# bms_AFE_R00.net
KiCad netlist of a schematic drawn in Altium Designer
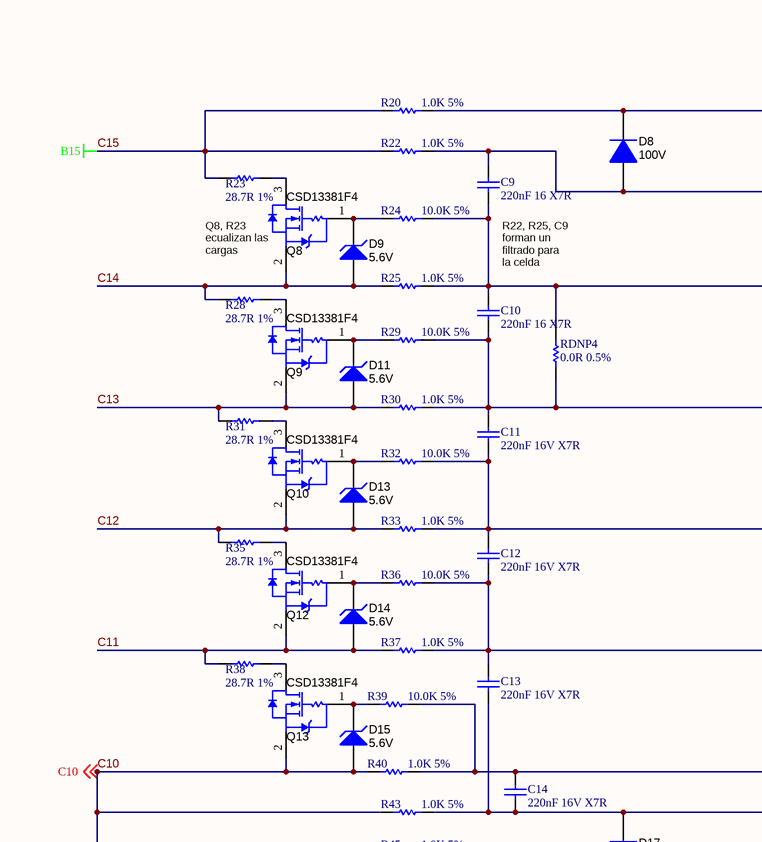
[diagram p0: bms_AFE_R00.SchDoc, top left]
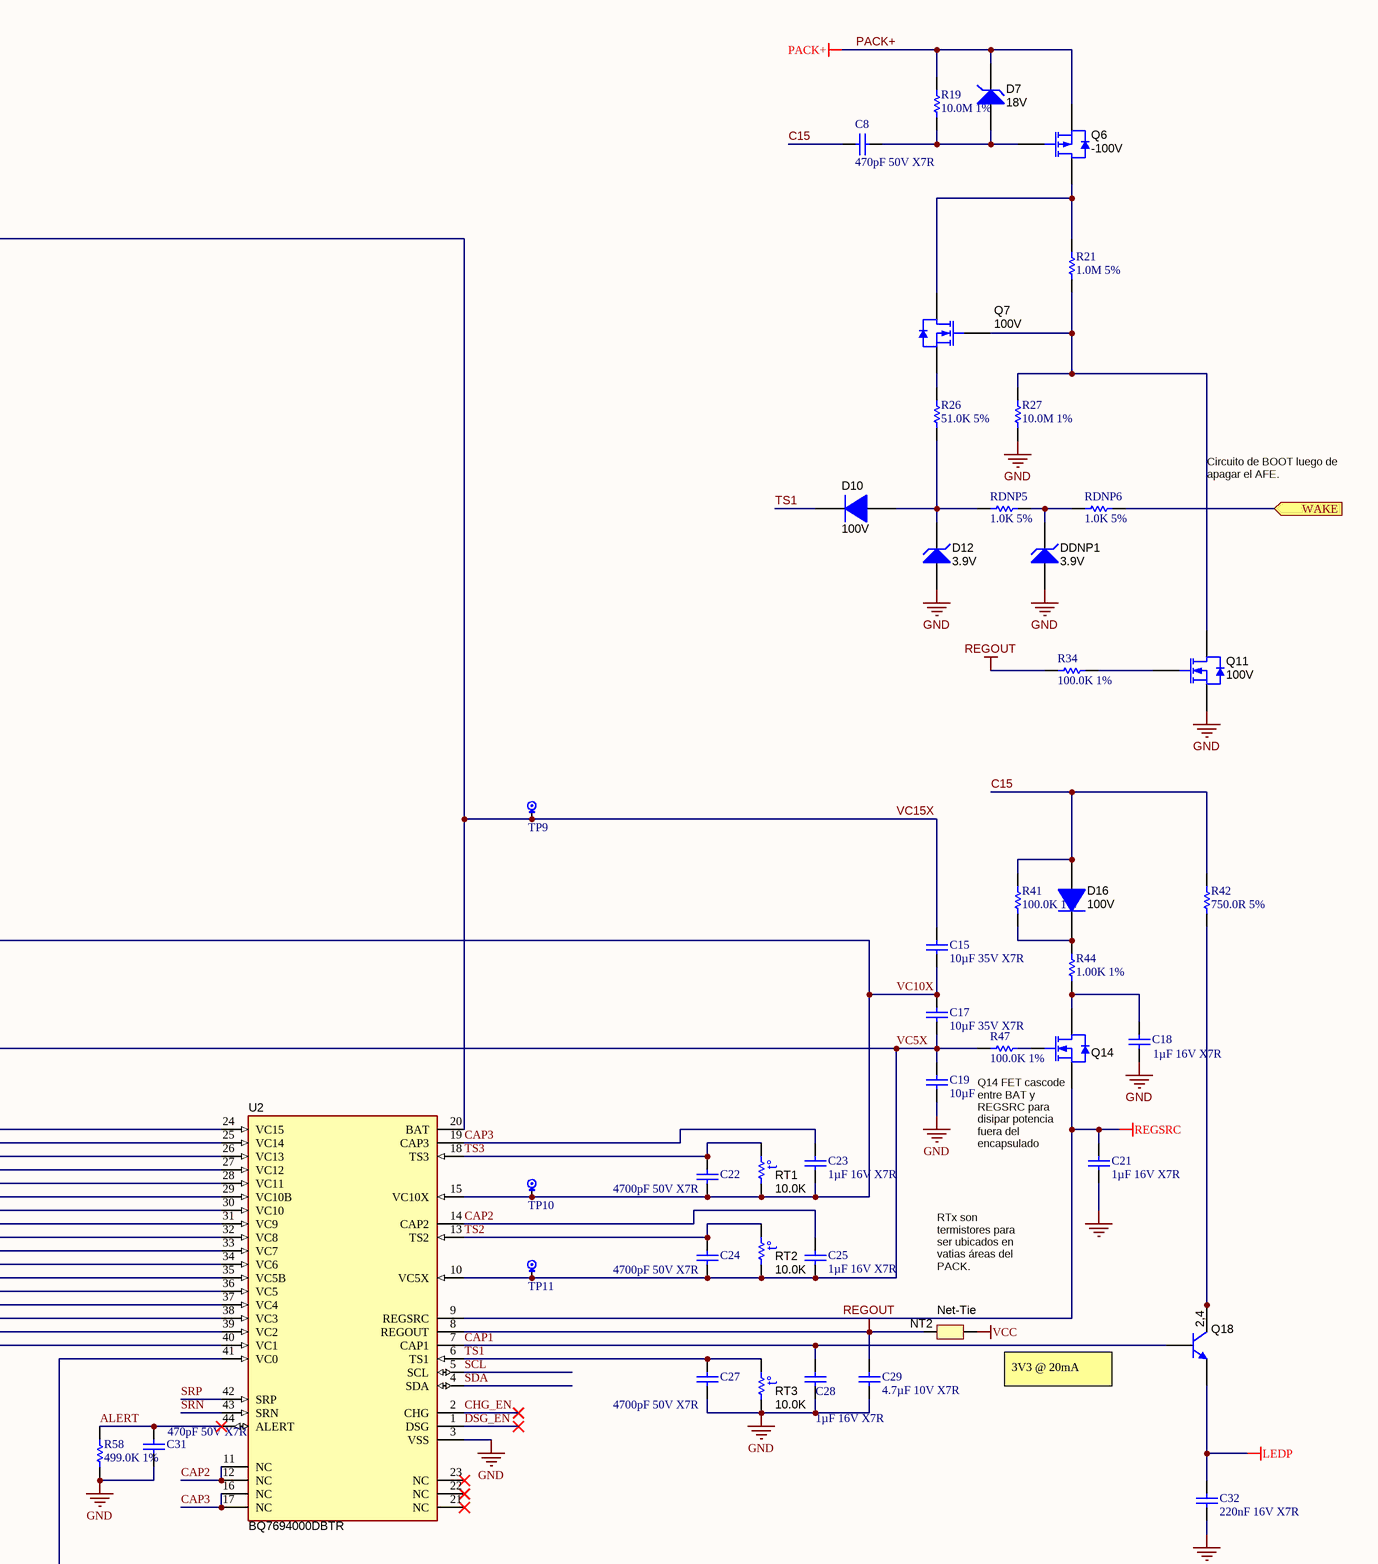
[diagram p1: bms_AFE_R00.SchDoc, top right]
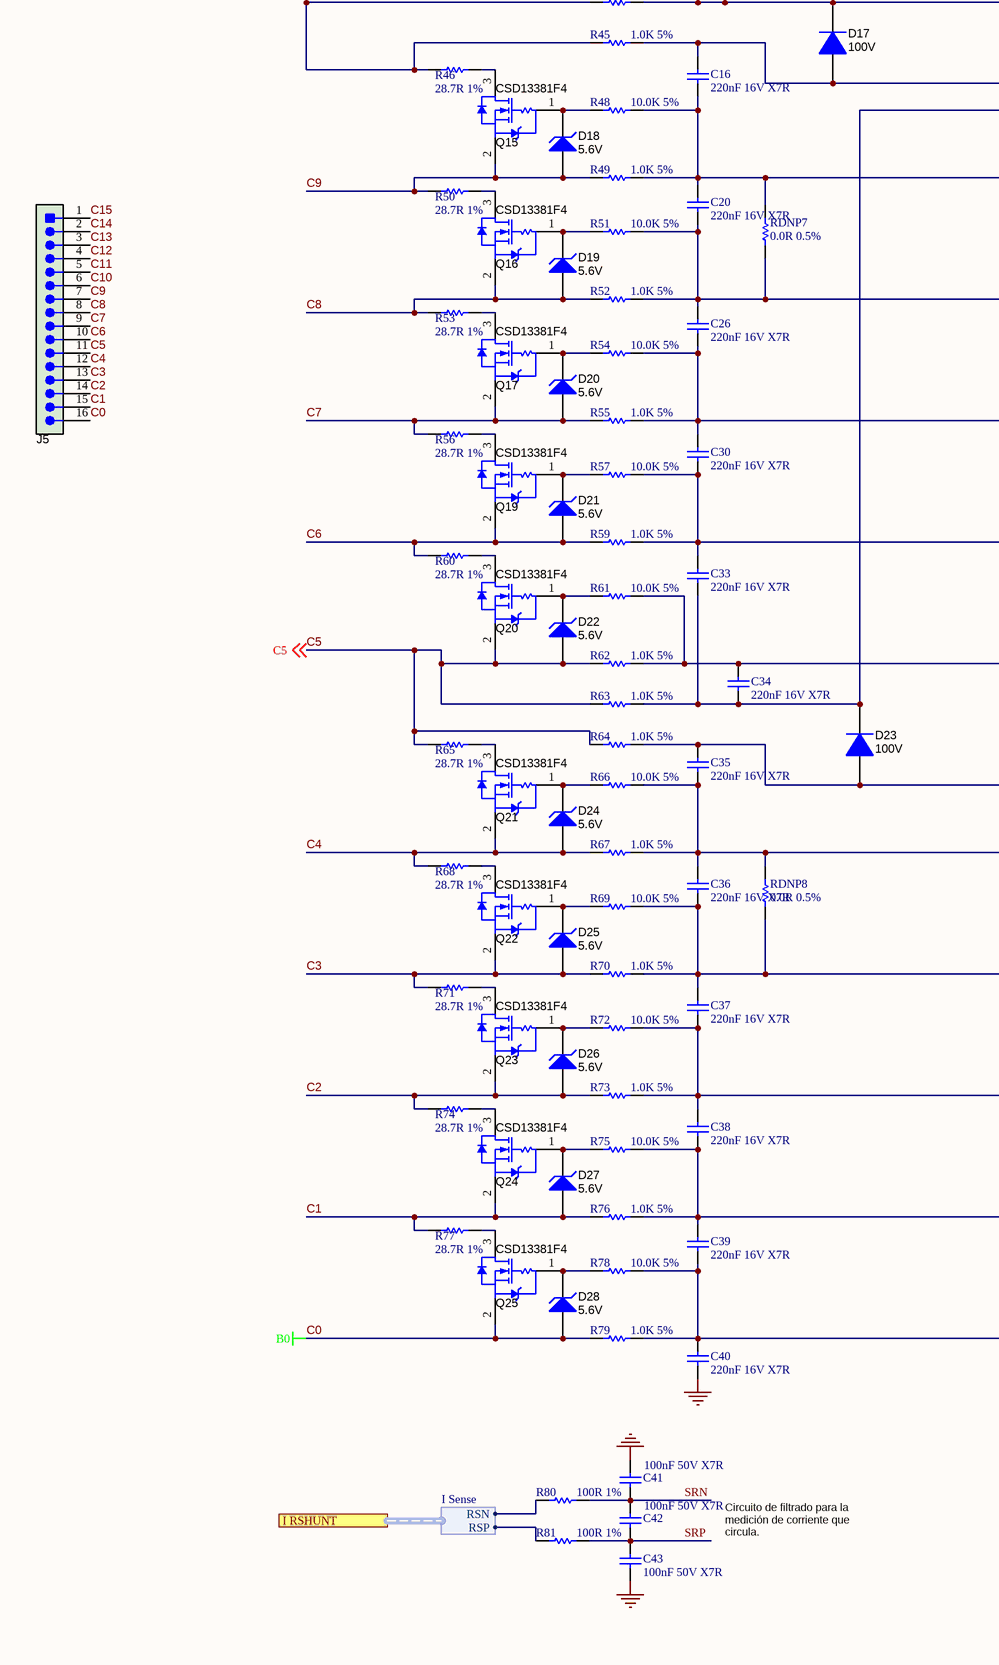
[diagram p2: bms_AFE_R00.SchDoc, bottom left]
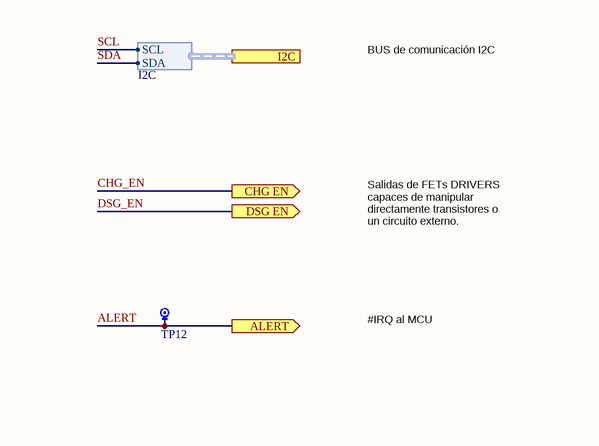
[diagram p3: bms_AFE_R00.SchDoc, bottom right]

(export (version "E")
  (design (tool "Eeschema 10.0.6"))
  (components
    (comp (ref "C8")
      (value "470pF 50V X7R")
      (footprint "C0603")
      (description "Capacitor")
      (libsource (lib "capacitors") (part "Cap 0603"))
    )
    (comp (ref "C9")
      (value "220nF 16 X7R")
      (footprint "C0603")
      (description "Capacitor")
      (libsource (lib "capacitors") (part "Cap 0603"))
    )
    (comp (ref "C10")
      (value "220nF 16 X7R")
      (footprint "C0603")
      (description "Capacitor")
      (libsource (lib "capacitors") (part "Cap 0603"))
    )
    (comp (ref "C11")
      (value "220nF 16V X7R")
      (footprint "C0603")
      (description "Capacitor")
      (libsource (lib "capacitors") (part "Cap 0603"))
    )
    (comp (ref "C12")
      (value "220nF 16V X7R")
      (footprint "C0603")
      (description "Capacitor")
      (libsource (lib "capacitors") (part "Cap 0603"))
    )
    (comp (ref "C13")
      (value "220nF 16V X7R")
      (footprint "C0603")
      (description "Capacitor")
      (libsource (lib "capacitors") (part "Cap 0603"))
    )
    (comp (ref "C14")
      (value "220nF 16V X7R")
      (footprint "C0603")
      (description "Capacitor")
      (libsource (lib "capacitors") (part "Cap 0603"))
    )
    (comp (ref "C15")
      (value "10µF 35V X7R")
      (footprint "1210_270")
      (description "Capacitor")
      (libsource (lib "capacitors") (part "Cap 1210"))
    )
    (comp (ref "C16")
      (value "220nF 16V X7R")
      (footprint "C0603")
      (description "Capacitor")
      (libsource (lib "capacitors") (part "Cap 0603"))
    )
    (comp (ref "C17")
      (value "10µF 35V X7R")
      (footprint "1210_270")
      (description "Capacitor")
      (libsource (lib "capacitors") (part "Cap 1210"))
    )
    (comp (ref "C18")
      (value "1µF 16V X7R")
      (footprint "0805_HV_2")
      (description "Capacitor")
      (libsource (lib "capacitors") (part "Cap 0805_HV"))
    )
    (comp (ref "C19")
      (value "10µF")
      (footprint "1210_270")
      (description "Capacitor")
      (libsource (lib "capacitors") (part "Cap 1210"))
    )
    (comp (ref "C20")
      (value "220nF 16V X7R")
      (footprint "C0603")
      (description "Capacitor")
      (libsource (lib "capacitors") (part "Cap 0603"))
    )
    (comp (ref "C21")
      (value "1µF 16V X7R")
      (footprint "0805")
      (description "Capacitor")
      (libsource (lib "capacitors") (part "Cap 0805"))
    )
    (comp (ref "C22")
      (value "4700pF 50V X7R")
      (footprint "C0603")
      (description "Capacitor")
      (libsource (lib "capacitors") (part "Cap 0603"))
    )
    (comp (ref "C23")
      (value "1µF 16V X7R")
      (footprint "C0603")
      (description "Capacitor")
      (libsource (lib "capacitors") (part "Cap 0603"))
    )
    (comp (ref "C24")
      (value "4700pF 50V X7R")
      (footprint "C0603")
      (description "Capacitor")
      (libsource (lib "capacitors") (part "Cap 0603"))
    )
    (comp (ref "C25")
      (value "1µF 16V X7R")
      (footprint "C0603")
      (description "Capacitor")
      (libsource (lib "capacitors") (part "Cap 0603"))
    )
    (comp (ref "C26")
      (value "220nF 16V X7R")
      (footprint "C0603")
      (description "Capacitor")
      (libsource (lib "capacitors") (part "Cap 0603"))
    )
    (comp (ref "C27")
      (value "4700pF 50V X7R")
      (footprint "C0603")
      (description "Capacitor")
      (libsource (lib "capacitors") (part "Cap 0603"))
    )
    (comp (ref "C28")
      (value "1µF 16V X7R")
      (footprint "C0603")
      (description "Capacitor")
      (libsource (lib "capacitors") (part "Cap 0603"))
    )
    (comp (ref "C29")
      (value "4.7µF 10V X7R")
      (footprint "0805_HV_2")
      (description "Capacitor")
      (libsource (lib "capacitors") (part "Cap 0805_HV"))
    )
    (comp (ref "C30")
      (value "220nF 16V X7R")
      (footprint "C0603")
      (description "Capacitor")
      (libsource (lib "capacitors") (part "Cap 0603"))
    )
    (comp (ref "C31")
      (value "470pF 50V X7R")
      (footprint "C0603")
      (description "Capacitor")
      (libsource (lib "capacitors") (part "Cap 0603"))
    )
    (comp (ref "C32")
      (value "220nF 16V X7R")
      (footprint "C0603")
      (description "Capacitor")
      (libsource (lib "capacitors") (part "Cap 0603"))
    )
    (comp (ref "C33")
      (value "220nF 16V X7R")
      (footprint "C0603")
      (description "Capacitor")
      (libsource (lib "capacitors") (part "Cap 0603"))
    )
    (comp (ref "C34")
      (value "220nF 16V X7R")
      (footprint "C0603")
      (description "Capacitor")
      (libsource (lib "capacitors") (part "Cap 0603"))
    )
    (comp (ref "C35")
      (value "220nF 16V X7R")
      (footprint "C0603")
      (description "Capacitor")
      (libsource (lib "capacitors") (part "Cap 0603"))
    )
    (comp (ref "C36")
      (value "220nF 16V X7R")
      (footprint "C0603")
      (description "Capacitor")
      (libsource (lib "capacitors") (part "Cap 0603"))
    )
    (comp (ref "C37")
      (value "220nF 16V X7R")
      (footprint "C0603")
      (description "Capacitor")
      (libsource (lib "capacitors") (part "Cap 0603"))
    )
    (comp (ref "C38")
      (value "220nF 16V X7R")
      (footprint "C0603")
      (description "Capacitor")
      (libsource (lib "capacitors") (part "Cap 0603"))
    )
    (comp (ref "C39")
      (value "220nF 16V X7R")
      (footprint "C0603")
      (description "Capacitor")
      (libsource (lib "capacitors") (part "Cap 0603"))
    )
    (comp (ref "C40")
      (value "220nF 16V X7R")
      (footprint "C0603")
      (description "Capacitor")
      (libsource (lib "capacitors") (part "Cap 0603"))
    )
    (comp (ref "C41")
      (value "100nF 50V X7R")
      (footprint "C0603")
      (description "Capacitor")
      (libsource (lib "capacitors") (part "Cap 0603"))
    )
    (comp (ref "C42")
      (value "100nF 50V X7R")
      (footprint "C0603")
      (description "Capacitor")
      (libsource (lib "capacitors") (part "Cap 0603"))
    )
    (comp (ref "C43")
      (value "100nF 50V X7R")
      (footprint "C0603")
      (description "Capacitor")
      (libsource (lib "capacitors") (part "Cap 0603"))
    )
    (comp (ref "D7")
      (value "18V")
      (footprint "sod-323")
      (description "Diode, Zener, 18 V, 200 mW, SOD-323")
      (fields
        (field (name "PARTNUMBER") "MMSZ5248BS-7-F")
        (field (name "MANUFACTURER") "Diodes Inc.")
        (field (name "SYMBOLCREATOR") "a0412235")
        (field (name "PUBLISHER") "Texas Instruments")
      )
      (libsource (lib "diodes") (part "MMSZ5248BS-7-F"))
    )
    (comp (ref "D8")
      (value "100V")
      (footprint "SOD-123")
      (description "Diode, Ultrafast, 100V, 0.15A, SOD-123")
      (fields
        (field (name "PARTNUMBER") "1N4148W-7-F")
        (field (name "MANUFACTURER") "Diodes Inc.")
        (field (name "PUBLISHER") "Texas Instruments")
      )
      (libsource (lib "diodes") (part "1N4148W-7-F"))
    )
    (comp (ref "D9")
      (value "5.6V")
      (footprint "sod-323")
      (description "Diode, Zener, 5.6V, 200mW, SOD-323")
      (fields
        (field (name "PARTNUMBER") "MMSZ5232BS-7-F")
        (field (name "MANUFACTURER") "Diodes Inc.")
        (field (name "PUBLISHER") "Texas Instruments")
      )
      (libsource (lib "diodes") (part "MMSZ5232BS-7-F"))
    )
    (comp (ref "D10")
      (value "100V")
      (footprint "SOD-123")
      (description "Diode, Ultrafast, 100V, 0.15A, SOD-123")
      (fields
        (field (name "PARTNUMBER") "1N4148W-7-F")
        (field (name "MANUFACTURER") "Diodes Inc.")
        (field (name "PUBLISHER") "Texas Instruments")
      )
      (libsource (lib "diodes") (part "1N4148W-7-F"))
    )
    (comp (ref "D11")
      (value "5.6V")
      (footprint "sod-323")
      (description "Diode, Zener, 5.6V, 200mW, SOD-323")
      (fields
        (field (name "PARTNUMBER") "MMSZ5232BS-7-F")
        (field (name "MANUFACTURER") "Diodes Inc.")
        (field (name "PUBLISHER") "Texas Instruments")
      )
      (libsource (lib "diodes") (part "MMSZ5232BS-7-F"))
    )
    (comp (ref "D12")
      (value "3.9V")
      (footprint "sod-323")
      (description "Diode, Zener, 3.9 V, 200 mW, SOD-323")
      (fields
        (field (name "PARTNUMBER") "MMSZ5228BS-7-F")
        (field (name "MANUFACTURER") "Diodes Inc.")
        (field (name "SYMBOLCREATOR") "a0412235")
        (field (name "PUBLISHER") "Texas Instruments")
      )
      (libsource (lib "diodes") (part "MMSZ5228BS-7-F"))
    )
    (comp (ref "D13")
      (value "5.6V")
      (footprint "sod-323")
      (description "Diode, Zener, 5.6V, 200mW, SOD-323")
      (fields
        (field (name "PARTNUMBER") "MMSZ5232BS-7-F")
        (field (name "MANUFACTURER") "Diodes Inc.")
        (field (name "PUBLISHER") "Texas Instruments")
      )
      (libsource (lib "diodes") (part "MMSZ5232BS-7-F"))
    )
    (comp (ref "D14")
      (value "5.6V")
      (footprint "sod-323")
      (description "Diode, Zener, 5.6V, 200mW, SOD-323")
      (fields
        (field (name "PARTNUMBER") "MMSZ5232BS-7-F")
        (field (name "MANUFACTURER") "Diodes Inc.")
        (field (name "PUBLISHER") "Texas Instruments")
      )
      (libsource (lib "diodes") (part "MMSZ5232BS-7-F"))
    )
    (comp (ref "D15")
      (value "5.6V")
      (footprint "sod-323")
      (description "Diode, Zener, 5.6V, 200mW, SOD-323")
      (fields
        (field (name "PARTNUMBER") "MMSZ5232BS-7-F")
        (field (name "MANUFACTURER") "Diodes Inc.")
        (field (name "PUBLISHER") "Texas Instruments")
      )
      (libsource (lib "diodes") (part "MMSZ5232BS-7-F"))
    )
    (comp (ref "D16")
      (value "100V")
      (footprint "SOD-123")
      (description "Diode, Ultrafast, 100V, 0.15A, SOD-123")
      (fields
        (field (name "PARTNUMBER") "1N4148W-7-F")
        (field (name "MANUFACTURER") "Diodes Inc.")
        (field (name "PUBLISHER") "Texas Instruments")
      )
      (libsource (lib "diodes") (part "1N4148W-7-F"))
    )
    (comp (ref "D17")
      (value "100V")
      (footprint "SOD-123")
      (description "Diode, Ultrafast, 100V, 0.15A, SOD-123")
      (fields
        (field (name "PARTNUMBER") "1N4148W-7-F")
        (field (name "MANUFACTURER") "Diodes Inc.")
        (field (name "PUBLISHER") "Texas Instruments")
      )
      (libsource (lib "diodes") (part "1N4148W-7-F"))
    )
    (comp (ref "D18")
      (value "5.6V")
      (footprint "sod-323")
      (description "Diode, Zener, 5.6V, 200mW, SOD-323")
      (fields
        (field (name "PARTNUMBER") "MMSZ5232BS-7-F")
        (field (name "MANUFACTURER") "Diodes Inc.")
        (field (name "PUBLISHER") "Texas Instruments")
      )
      (libsource (lib "diodes") (part "MMSZ5232BS-7-F"))
    )
    (comp (ref "D19")
      (value "5.6V")
      (footprint "sod-323")
      (description "Diode, Zener, 5.6V, 200mW, SOD-323")
      (fields
        (field (name "PARTNUMBER") "MMSZ5232BS-7-F")
        (field (name "MANUFACTURER") "Diodes Inc.")
        (field (name "PUBLISHER") "Texas Instruments")
      )
      (libsource (lib "diodes") (part "MMSZ5232BS-7-F"))
    )
    (comp (ref "D20")
      (value "5.6V")
      (footprint "sod-323")
      (description "Diode, Zener, 5.6V, 200mW, SOD-323")
      (fields
        (field (name "PARTNUMBER") "MMSZ5232BS-7-F")
        (field (name "MANUFACTURER") "Diodes Inc.")
        (field (name "PUBLISHER") "Texas Instruments")
      )
      (libsource (lib "diodes") (part "MMSZ5232BS-7-F"))
    )
    (comp (ref "D21")
      (value "5.6V")
      (footprint "sod-323")
      (description "Diode, Zener, 5.6V, 200mW, SOD-323")
      (fields
        (field (name "PARTNUMBER") "MMSZ5232BS-7-F")
        (field (name "MANUFACTURER") "Diodes Inc.")
        (field (name "PUBLISHER") "Texas Instruments")
      )
      (libsource (lib "diodes") (part "MMSZ5232BS-7-F"))
    )
    (comp (ref "D22")
      (value "5.6V")
      (footprint "sod-323")
      (description "Diode, Zener, 5.6V, 200mW, SOD-323")
      (fields
        (field (name "PARTNUMBER") "MMSZ5232BS-7-F")
        (field (name "MANUFACTURER") "Diodes Inc.")
        (field (name "PUBLISHER") "Texas Instruments")
      )
      (libsource (lib "diodes") (part "MMSZ5232BS-7-F"))
    )
    (comp (ref "D23")
      (value "100V")
      (footprint "SOD-123")
      (description "Diode, Ultrafast, 100V, 0.15A, SOD-123")
      (fields
        (field (name "PARTNUMBER") "1N4148W-7-F")
        (field (name "MANUFACTURER") "Diodes Inc.")
        (field (name "PUBLISHER") "Texas Instruments")
      )
      (libsource (lib "diodes") (part "1N4148W-7-F"))
    )
    (comp (ref "D24")
      (value "5.6V")
      (footprint "sod-323")
      (description "Diode, Zener, 5.6V, 200mW, SOD-323")
      (fields
        (field (name "PARTNUMBER") "MMSZ5232BS-7-F")
        (field (name "MANUFACTURER") "Diodes Inc.")
        (field (name "PUBLISHER") "Texas Instruments")
      )
      (libsource (lib "diodes") (part "MMSZ5232BS-7-F"))
    )
    (comp (ref "D25")
      (value "5.6V")
      (footprint "sod-323")
      (description "Diode, Zener, 5.6V, 200mW, SOD-323")
      (fields
        (field (name "PARTNUMBER") "MMSZ5232BS-7-F")
        (field (name "MANUFACTURER") "Diodes Inc.")
        (field (name "PUBLISHER") "Texas Instruments")
      )
      (libsource (lib "diodes") (part "MMSZ5232BS-7-F"))
    )
    (comp (ref "D26")
      (value "5.6V")
      (footprint "sod-323")
      (description "Diode, Zener, 5.6V, 200mW, SOD-323")
      (fields
        (field (name "PARTNUMBER") "MMSZ5232BS-7-F")
        (field (name "MANUFACTURER") "Diodes Inc.")
        (field (name "PUBLISHER") "Texas Instruments")
      )
      (libsource (lib "diodes") (part "MMSZ5232BS-7-F"))
    )
    (comp (ref "D27")
      (value "5.6V")
      (footprint "sod-323")
      (description "Diode, Zener, 5.6V, 200mW, SOD-323")
      (fields
        (field (name "PARTNUMBER") "MMSZ5232BS-7-F")
        (field (name "MANUFACTURER") "Diodes Inc.")
        (field (name "PUBLISHER") "Texas Instruments")
      )
      (libsource (lib "diodes") (part "MMSZ5232BS-7-F"))
    )
    (comp (ref "D28")
      (value "5.6V")
      (footprint "sod-323")
      (description "Diode, Zener, 5.6V, 200mW, SOD-323")
      (fields
        (field (name "PARTNUMBER") "MMSZ5232BS-7-F")
        (field (name "MANUFACTURER") "Diodes Inc.")
        (field (name "PUBLISHER") "Texas Instruments")
      )
      (libsource (lib "diodes") (part "MMSZ5232BS-7-F"))
    )
    (comp (ref "DDNP1")
      (value "3.9V")
      (footprint "sod-323")
      (description "Diode, Zener, 3.9 V, 200 mW, SOD-323")
      (fields
        (field (name "PARTNUMBER") "MMSZ5228BS-7-F")
        (field (name "MANUFACTURER") "Diodes Inc.")
        (field (name "SYMBOLCREATOR") "a0412235")
        (field (name "PUBLISHER") "Texas Instruments")
      )
      (libsource (lib "diodes") (part "MMSZ5228BS-7-F"))
    )
    (comp (ref "J5")
      (value "395021011")
      (footprint "HEADER_395021016")
      (description "Terminal block, 3.5mm, 16x1, R/A, TH")
      (fields
        (field (name "MANUFACTURER") "Molex")
        (field (name "SYMBOLCREATOR") "a0799628")
        (field (name "PUBLISHER") "Texas Instruments")
      )
      (libsource (lib "connectors") (part "395021016"))
    )
    (comp (ref "NT2")
      (value "Net-Tie")
      (footprint "Net-Tie_50milWide_30milLong")
      (description "Single point connection between nets.")
      (fields (field (name "SYMBOLCREATOR") "codlsc") (field (name "PUBLISHER") "Texas Instruments"))
      (libsource (lib "connectors") (part "Net-Tie"))
    )
    (comp (ref "Q6")
      (value "-100V")
      (footprint "SOT-23")
      (description "MOSFET, P-CH, -100V, -0.6A, SOT-23")
      (fields
        (field (name "PARTNUMBER") "ZXMP10A13FTA")
        (field (name "MANUFACTURER") "Diodes Inc.")
        (field (name "PUBLISHER") "Texas Instruments")
      )
      (libsource (lib "pmos") (part "ZXMP10A13FTA"))
    )
    (comp (ref "Q7")
      (value "100V")
      (footprint "SOT-23")
      (description "MOSFET, N-CH, 100V, 0.17A, SOT-23")
      (fields
        (field (name "PARTNUMBER") "BSS123")
        (field (name "MANUFACTURER") "Fairchild Semiconductor")
        (field (name "PUBLISHER") "Texas Instruments")
      )
      (libsource (lib "nmos") (part "BSS123"))
    )
    (comp (ref "Q8")
      (value "CSD13381F4")
      (footprint "YJC0003A")
      (description "MOSFET, N/P-CH, 12 V, 2.1 A, 1.0x0.35x0.6mm")
      (fields
        (field (name "MANUFACTURER") "Texas Instruments")
        (field (name "SYMBOLCREATOR") "a0411947")
        (field (name "PUBLISHER") "Texas Instruments")
      )
      (libsource (lib "nmos") (part "CSD13381F4"))
    )
    (comp (ref "Q9")
      (value "CSD13381F4")
      (footprint "YJC0003A")
      (description "MOSFET, N/P-CH, 12 V, 2.1 A, 1.0x0.35x0.6mm")
      (fields
        (field (name "MANUFACTURER") "Texas Instruments")
        (field (name "SYMBOLCREATOR") "a0411947")
        (field (name "PUBLISHER") "Texas Instruments")
      )
      (libsource (lib "nmos") (part "CSD13381F4"))
    )
    (comp (ref "Q10")
      (value "CSD13381F4")
      (footprint "YJC0003A")
      (description "MOSFET, N/P-CH, 12 V, 2.1 A, 1.0x0.35x0.6mm")
      (fields
        (field (name "MANUFACTURER") "Texas Instruments")
        (field (name "SYMBOLCREATOR") "a0411947")
        (field (name "PUBLISHER") "Texas Instruments")
      )
      (libsource (lib "nmos") (part "CSD13381F4"))
    )
    (comp (ref "Q11")
      (value "100V")
      (footprint "SOT-23")
      (description "MOSFET, N-CH, 100V, 0.17A, SOT-23")
      (fields
        (field (name "PARTNUMBER") "BSS123")
        (field (name "MANUFACTURER") "Fairchild Semiconductor")
        (field (name "PUBLISHER") "Texas Instruments")
      )
      (libsource (lib "nmos") (part "BSS123"))
    )
    (comp (ref "Q12")
      (value "CSD13381F4")
      (footprint "YJC0003A")
      (description "MOSFET, N/P-CH, 12 V, 2.1 A, 1.0x0.35x0.6mm")
      (fields
        (field (name "MANUFACTURER") "Texas Instruments")
        (field (name "SYMBOLCREATOR") "a0411947")
        (field (name "PUBLISHER") "Texas Instruments")
      )
      (libsource (lib "nmos") (part "CSD13381F4"))
    )
    (comp (ref "Q13")
      (value "CSD13381F4")
      (footprint "YJC0003A")
      (description "MOSFET, N/P-CH, 12 V, 2.1 A, 1.0x0.35x0.6mm")
      (fields
        (field (name "MANUFACTURER") "Texas Instruments")
        (field (name "SYMBOLCREATOR") "a0411947")
        (field (name "PUBLISHER") "Texas Instruments")
      )
      (libsource (lib "nmos") (part "CSD13381F4"))
    )
    (comp (ref "Q14")
      (value "BST82,215")
      (footprint "SOT-23")
      (description "MOSFET, N-CH, 100 V, 0.19 A, SOT-23")
      (fields
        (field (name "MANUFACTURER") "NXP Semiconductor")
        (field (name "PUBLISHER") "Texas Instruments")
      )
      (libsource (lib "nmos") (part "BST82,215"))
    )
    (comp (ref "Q15")
      (value "CSD13381F4")
      (footprint "YJC0003A")
      (description "MOSFET, N/P-CH, 12 V, 2.1 A, 1.0x0.35x0.6mm")
      (fields
        (field (name "MANUFACTURER") "Texas Instruments")
        (field (name "SYMBOLCREATOR") "a0411947")
        (field (name "PUBLISHER") "Texas Instruments")
      )
      (libsource (lib "nmos") (part "CSD13381F4"))
    )
    (comp (ref "Q16")
      (value "CSD13381F4")
      (footprint "YJC0003A")
      (description "MOSFET, N/P-CH, 12 V, 2.1 A, 1.0x0.35x0.6mm")
      (fields
        (field (name "MANUFACTURER") "Texas Instruments")
        (field (name "SYMBOLCREATOR") "a0411947")
        (field (name "PUBLISHER") "Texas Instruments")
      )
      (libsource (lib "nmos") (part "CSD13381F4"))
    )
    (comp (ref "Q17")
      (value "CSD13381F4")
      (footprint "YJC0003A")
      (description "MOSFET, N/P-CH, 12 V, 2.1 A, 1.0x0.35x0.6mm")
      (fields
        (field (name "MANUFACTURER") "Texas Instruments")
        (field (name "SYMBOLCREATOR") "a0411947")
        (field (name "PUBLISHER") "Texas Instruments")
      )
      (libsource (lib "nmos") (part "CSD13381F4"))
    )
    (comp (ref "Q18")
      (value "ZXTN19100CZTA")
      (footprint "SOT-89-3")
      (description "Transistor, NPN, 100 V, 5.25 A, SOT-89")
      (fields
        (field (name "MANUFACTURER") "Diodes Inc.")
        (field (name "SYMBOLCREATOR") "a0412235")
        (field (name "PUBLISHER") "Texas Instruments")
      )
      (libsource (lib "npn") (part "ZXTN19100CZTA, Diodes Inc."))
    )
    (comp (ref "Q19")
      (value "CSD13381F4")
      (footprint "YJC0003A")
      (description "MOSFET, N/P-CH, 12 V, 2.1 A, 1.0x0.35x0.6mm")
      (fields
        (field (name "MANUFACTURER") "Texas Instruments")
        (field (name "SYMBOLCREATOR") "a0411947")
        (field (name "PUBLISHER") "Texas Instruments")
      )
      (libsource (lib "nmos") (part "CSD13381F4"))
    )
    (comp (ref "Q20")
      (value "CSD13381F4")
      (footprint "YJC0003A")
      (description "MOSFET, N/P-CH, 12 V, 2.1 A, 1.0x0.35x0.6mm")
      (fields
        (field (name "MANUFACTURER") "Texas Instruments")
        (field (name "SYMBOLCREATOR") "a0411947")
        (field (name "PUBLISHER") "Texas Instruments")
      )
      (libsource (lib "nmos") (part "CSD13381F4"))
    )
    (comp (ref "Q21")
      (value "CSD13381F4")
      (footprint "YJC0003A")
      (description "MOSFET, N/P-CH, 12 V, 2.1 A, 1.0x0.35x0.6mm")
      (fields
        (field (name "MANUFACTURER") "Texas Instruments")
        (field (name "SYMBOLCREATOR") "a0411947")
        (field (name "PUBLISHER") "Texas Instruments")
      )
      (libsource (lib "nmos") (part "CSD13381F4"))
    )
    (comp (ref "Q22")
      (value "CSD13381F4")
      (footprint "YJC0003A")
      (description "MOSFET, N/P-CH, 12 V, 2.1 A, 1.0x0.35x0.6mm")
      (fields
        (field (name "MANUFACTURER") "Texas Instruments")
        (field (name "SYMBOLCREATOR") "a0411947")
        (field (name "PUBLISHER") "Texas Instruments")
      )
      (libsource (lib "nmos") (part "CSD13381F4"))
    )
    (comp (ref "Q23")
      (value "CSD13381F4")
      (footprint "YJC0003A")
      (description "MOSFET, N/P-CH, 12 V, 2.1 A, 1.0x0.35x0.6mm")
      (fields
        (field (name "MANUFACTURER") "Texas Instruments")
        (field (name "SYMBOLCREATOR") "a0411947")
        (field (name "PUBLISHER") "Texas Instruments")
      )
      (libsource (lib "nmos") (part "CSD13381F4"))
    )
    (comp (ref "Q24")
      (value "CSD13381F4")
      (footprint "YJC0003A")
      (description "MOSFET, N/P-CH, 12 V, 2.1 A, 1.0x0.35x0.6mm")
      (fields
        (field (name "MANUFACTURER") "Texas Instruments")
        (field (name "SYMBOLCREATOR") "a0411947")
        (field (name "PUBLISHER") "Texas Instruments")
      )
      (libsource (lib "nmos") (part "CSD13381F4"))
    )
    (comp (ref "Q25")
      (value "CSD13381F4")
      (footprint "YJC0003A")
      (description "MOSFET, N/P-CH, 12 V, 2.1 A, 1.0x0.35x0.6mm")
      (fields
        (field (name "MANUFACTURER") "Texas Instruments")
        (field (name "SYMBOLCREATOR") "a0411947")
        (field (name "PUBLISHER") "Texas Instruments")
      )
      (libsource (lib "nmos") (part "CSD13381F4"))
    )
    (comp (ref "R19")
      (value "10.0M 1%")
      (footprint "R0603")
      (description "Resistor")
      (libsource (lib "resistors") (part "Res"))
    )
    (comp (ref "R20")
      (value "1.0K 5%")
      (footprint "R0603")
      (description "Resistor")
      (libsource (lib "resistors") (part "Res"))
    )
    (comp (ref "R21")
      (value "1.0M 5%")
      (footprint "R0603")
      (description "Resistor")
      (libsource (lib "resistors") (part "Res"))
    )
    (comp (ref "R22")
      (value "1.0K 5%")
      (footprint "R0603")
      (description "Resistor")
      (libsource (lib "resistors") (part "Res"))
    )
    (comp (ref "R23")
      (value "28.7R 1%")
      (footprint "2512")
      (description "Resistor")
      (libsource (lib "resistors") (part "Res"))
    )
    (comp (ref "R24")
      (value "10.0K 5%")
      (footprint "R0603")
      (description "Resistor")
      (libsource (lib "resistors") (part "Res"))
    )
    (comp (ref "R25")
      (value "1.0K 5%")
      (footprint "R0603")
      (description "Resistor")
      (libsource (lib "resistors") (part "Res"))
    )
    (comp (ref "R26")
      (value "51.0K 5%")
      (footprint "R0603")
      (description "Resistor")
      (libsource (lib "resistors") (part "Res"))
    )
    (comp (ref "R27")
      (value "10.0M 1%")
      (footprint "R0603")
      (description "Resistor")
      (libsource (lib "resistors") (part "Res"))
    )
    (comp (ref "R28")
      (value "28.7R 1%")
      (footprint "2512")
      (description "Resistor")
      (libsource (lib "resistors") (part "Res"))
    )
    (comp (ref "R29")
      (value "10.0K 5%")
      (footprint "R0603")
      (description "Resistor")
      (libsource (lib "resistors") (part "Res"))
    )
    (comp (ref "R30")
      (value "1.0K 5%")
      (footprint "R0603")
      (description "Resistor")
      (libsource (lib "resistors") (part "Res"))
    )
    (comp (ref "R31")
      (value "28.7R 1%")
      (footprint "2512")
      (description "Resistor")
      (libsource (lib "resistors") (part "Res"))
    )
    (comp (ref "R32")
      (value "10.0K 5%")
      (footprint "R0603")
      (description "Resistor")
      (libsource (lib "resistors") (part "Res"))
    )
    (comp (ref "R33")
      (value "1.0K 5%")
      (footprint "R0603")
      (description "Resistor")
      (libsource (lib "resistors") (part "Res"))
    )
    (comp (ref "R34")
      (value "100.0K 1%")
      (footprint "0805_HV_2")
      (description "Resistor")
      (libsource (lib "resistors") (part "Res"))
    )
    (comp (ref "R35")
      (value "28.7R 1%")
      (footprint "2512")
      (description "Resistor")
      (libsource (lib "resistors") (part "Res"))
    )
    (comp (ref "R36")
      (value "10.0K 5%")
      (footprint "R0603")
      (description "Resistor")
      (libsource (lib "resistors") (part "Res"))
    )
    (comp (ref "R37")
      (value "1.0K 5%")
      (footprint "R0603")
      (description "Resistor")
      (libsource (lib "resistors") (part "Res"))
    )
    (comp (ref "R38")
      (value "28.7R 1%")
      (footprint "2512")
      (description "Resistor")
      (libsource (lib "resistors") (part "Res"))
    )
    (comp (ref "R39")
      (value "10.0K 5%")
      (footprint "R0603")
      (description "Resistor")
      (libsource (lib "resistors") (part "Res"))
    )
    (comp (ref "R40")
      (value "1.0K 5%")
      (footprint "R0603")
      (description "Resistor")
      (libsource (lib "resistors") (part "Res"))
    )
    (comp (ref "R41")
      (value "100.0K 1%")
      (footprint "0805_HV_2")
      (description "Resistor")
      (libsource (lib "resistors") (part "Res"))
    )
    (comp (ref "R42")
      (value "750.0R 5%")
      (footprint "2010")
      (description "Resistor")
      (libsource (lib "resistors") (part "Res"))
    )
    (comp (ref "R43")
      (value "1.0K 5%")
      (footprint "R0603")
      (description "Resistor")
      (libsource (lib "resistors") (part "Res"))
    )
    (comp (ref "R44")
      (value "1.00K 1%")
      (footprint "2010")
      (description "Resistor")
      (libsource (lib "resistors") (part "Res"))
    )
    (comp (ref "R45")
      (value "1.0K 5%")
      (footprint "R0603")
      (description "Resistor")
      (libsource (lib "resistors") (part "Res"))
    )
    (comp (ref "R46")
      (value "28.7R 1%")
      (footprint "2512")
      (description "Resistor")
      (libsource (lib "resistors") (part "Res"))
    )
    (comp (ref "R47")
      (value "100.0K 1%")
      (footprint "0805_HV_2")
      (description "Resistor")
      (libsource (lib "resistors") (part "Res"))
    )
    (comp (ref "R48")
      (value "10.0K 5%")
      (footprint "R0603")
      (description "Resistor")
      (libsource (lib "resistors") (part "Res"))
    )
    (comp (ref "R49")
      (value "1.0K 5%")
      (footprint "R0603")
      (description "Resistor")
      (libsource (lib "resistors") (part "Res"))
    )
    (comp (ref "R50")
      (value "28.7R 1%")
      (footprint "2512")
      (description "Resistor")
      (libsource (lib "resistors") (part "Res"))
    )
    (comp (ref "R51")
      (value "10.0K 5%")
      (footprint "R0603")
      (description "Resistor")
      (libsource (lib "resistors") (part "Res"))
    )
    (comp (ref "R52")
      (value "1.0K 5%")
      (footprint "R0603")
      (description "Resistor")
      (libsource (lib "resistors") (part "Res"))
    )
    (comp (ref "R53")
      (value "28.7R 1%")
      (footprint "2512")
      (description "Resistor")
      (libsource (lib "resistors") (part "Res"))
    )
    (comp (ref "R54")
      (value "10.0K 5%")
      (footprint "R0603")
      (description "Resistor")
      (libsource (lib "resistors") (part "Res"))
    )
    (comp (ref "R55")
      (value "1.0K 5%")
      (footprint "R0603")
      (description "Resistor")
      (libsource (lib "resistors") (part "Res"))
    )
    (comp (ref "R56")
      (value "28.7R 1%")
      (footprint "2512")
      (description "Resistor")
      (libsource (lib "resistors") (part "Res"))
    )
    (comp (ref "R57")
      (value "10.0K 5%")
      (footprint "R0603")
      (description "Resistor")
      (libsource (lib "resistors") (part "Res"))
    )
    (comp (ref "R58")
      (value "499.0K 1%")
      (footprint "R0603")
      (description "Resistor")
      (libsource (lib "resistors") (part "Res"))
    )
    (comp (ref "R59")
      (value "1.0K 5%")
      (footprint "R0603")
      (description "Resistor")
      (libsource (lib "resistors") (part "Res"))
    )
    (comp (ref "R60")
      (value "28.7R 1%")
      (footprint "2512")
      (description "Resistor")
      (libsource (lib "resistors") (part "Res"))
    )
    (comp (ref "R61")
      (value "10.0K 5%")
      (footprint "R0603")
      (description "Resistor")
      (libsource (lib "resistors") (part "Res"))
    )
    (comp (ref "R62")
      (value "1.0K 5%")
      (footprint "R0603")
      (description "Resistor")
      (libsource (lib "resistors") (part "Res"))
    )
    (comp (ref "R63")
      (value "1.0K 5%")
      (footprint "R0603")
      (description "Resistor")
      (libsource (lib "resistors") (part "Res"))
    )
    (comp (ref "R64")
      (value "1.0K 5%")
      (footprint "R0603")
      (description "Resistor")
      (libsource (lib "resistors") (part "Res"))
    )
    (comp (ref "R65")
      (value "28.7R 1%")
      (footprint "2512")
      (description "Resistor")
      (libsource (lib "resistors") (part "Res"))
    )
    (comp (ref "R66")
      (value "10.0K 5%")
      (footprint "R0603")
      (description "Resistor")
      (libsource (lib "resistors") (part "Res"))
    )
    (comp (ref "R67")
      (value "1.0K 5%")
      (footprint "R0603")
      (description "Resistor")
      (libsource (lib "resistors") (part "Res"))
    )
    (comp (ref "R68")
      (value "28.7R 1%")
      (footprint "2512")
      (description "Resistor")
      (libsource (lib "resistors") (part "Res"))
    )
    (comp (ref "R69")
      (value "10.0K 5%")
      (footprint "R0603")
      (description "Resistor")
      (libsource (lib "resistors") (part "Res"))
    )
    (comp (ref "R70")
      (value "1.0K 5%")
      (footprint "R0603")
      (description "Resistor")
      (libsource (lib "resistors") (part "Res"))
    )
    (comp (ref "R71")
      (value "28.7R 1%")
      (footprint "2512")
      (description "Resistor")
      (libsource (lib "resistors") (part "Res"))
    )
    (comp (ref "R72")
      (value "10.0K 5%")
      (footprint "R0603")
      (description "Resistor")
      (libsource (lib "resistors") (part "Res"))
    )
    (comp (ref "R73")
      (value "1.0K 5%")
      (footprint "R0603")
      (description "Resistor")
      (libsource (lib "resistors") (part "Res"))
    )
    (comp (ref "R74")
      (value "28.7R 1%")
      (footprint "2512")
      (description "Resistor")
      (libsource (lib "resistors") (part "Res"))
    )
    (comp (ref "R75")
      (value "10.0K 5%")
      (footprint "R0603")
      (description "Resistor")
      (libsource (lib "resistors") (part "Res"))
    )
    (comp (ref "R76")
      (value "1.0K 5%")
      (footprint "R0603")
      (description "Resistor")
      (libsource (lib "resistors") (part "Res"))
    )
    (comp (ref "R77")
      (value "28.7R 1%")
      (footprint "2512")
      (description "Resistor")
      (libsource (lib "resistors") (part "Res"))
    )
    (comp (ref "R78")
      (value "10.0K 5%")
      (footprint "R0603")
      (description "Resistor")
      (libsource (lib "resistors") (part "Res"))
    )
    (comp (ref "R79")
      (value "1.0K 5%")
      (footprint "R0603")
      (description "Resistor")
      (libsource (lib "resistors") (part "Res"))
    )
    (comp (ref "R80")
      (value "100R 1%")
      (footprint "0805_HV_2")
      (description "Resistor")
      (libsource (lib "resistors") (part "Res 0805_HV"))
    )
    (comp (ref "R81")
      (value "100R 1%")
      (footprint "0805_HV_2")
      (description "Resistor")
      (libsource (lib "resistors") (part "Res 0805_HV"))
    )
    (comp (ref "RDNP4")
      (value "0.0R 0.5%")
      (footprint "R0603")
      (description "Resistor")
      (libsource (lib "resistors") (part "Res"))
    )
    (comp (ref "RDNP5")
      (value "1.0K 5%")
      (footprint "R0603")
      (description "Resistor")
      (libsource (lib "resistors") (part "Res"))
    )
    (comp (ref "RDNP6")
      (value "1.0K 5%")
      (footprint "R0603")
      (description "Resistor")
      (libsource (lib "resistors") (part "Res"))
    )
    (comp (ref "RDNP7")
      (value "0.0R 0.5%")
      (footprint "R0603")
      (description "Resistor")
      (libsource (lib "resistors") (part "Res"))
    )
    (comp (ref "RDNP8")
      (value "0.0R 0.5%")
      (footprint "R0603")
      (description "Resistor")
      (libsource (lib "resistors") (part "Res"))
    )
    (comp (ref "RT1")
      (value "10.0K")
      (footprint "Thermistor_103AT-2")
      (description "Thermistor NTC, 10.0k ohm, 1%, Disc, 5x8.4 mm")
      (fields
        (field (name "MANUFACTURER") "SEMITEC Corporation")
        (field (name "PARTNUMBER") "103AT-2")
        (field (name "PUBLISHER") "Texas Instruments")
      )
      (libsource (lib "sensors") (part "103AT-2"))
    )
    (comp (ref "RT2")
      (value "10.0K")
      (footprint "Thermistor_103AT-2")
      (description "Thermistor NTC, 10.0k ohm, 1%, Disc, 5x8.4 mm")
      (fields
        (field (name "MANUFACTURER") "SEMITEC Corporation")
        (field (name "PARTNUMBER") "103AT-2")
        (field (name "PUBLISHER") "Texas Instruments")
      )
      (libsource (lib "sensors") (part "103AT-2"))
    )
    (comp (ref "RT3")
      (value "10.0K")
      (footprint "Thermistor_103AT-2")
      (description "Thermistor NTC, 10.0k ohm, 1%, Disc, 5x8.4 mm")
      (fields
        (field (name "MANUFACTURER") "SEMITEC Corporation")
        (field (name "PARTNUMBER") "103AT-2")
        (field (name "PUBLISHER") "Texas Instruments")
      )
      (libsource (lib "sensors") (part "103AT-2"))
    )
    (comp (ref "TP9")
      (value "Test Point")
      (footprint "TEST POINT SMD 1")
      (libsource (lib "connectors") (part "Test Point"))
    )
    (comp (ref "TP10")
      (value "Test Point")
      (footprint "TEST POINT SMD 1")
      (libsource (lib "connectors") (part "Test Point"))
    )
    (comp (ref "TP11")
      (value "Test Point")
      (footprint "TEST POINT SMD 1")
      (libsource (lib "connectors") (part "Test Point"))
    )
    (comp (ref "TP12")
      (value "Test Point")
      (footprint "TEST POINT SMD 1")
      (libsource (lib "connectors") (part "Test Point"))
    )
    (comp (ref "U2")
      (value "BQ7694000DBTR")
      (footprint "DBT0044A_N")
      (description "Battery Monitor for Lithium-Ion and Phosphate Battery Packs, DBT0044A")
      (fields
        (field (name "ALTERNATE PARTNUMBER") "BQ7694000DBT")
        (field (name "MANUFACTURER") "Texas Instruments")
        (field (name "SYMBOLCREATOR") "a0412235")
        (field (name "PUBLISHER") "Texas Instruments")
      )
      (libsource (lib "integrated_circuits") (part "BQ7694000DBTR"))
    )
  )
  (nets
    (net (code "4") (name "/ALERT") (class "Default")
      (node (ref "C31") (pin "2") (pinfunction "2_2") (pintype "passive"))
      (node (ref "R58") (pin "2") (pinfunction "2_2") (pintype "passive"))
      (node (ref "TP12") (pin "1") (pinfunction "1_1") (pintype "passive"))
      (node (ref "U2") (pin "44") (pinfunction "ALERT_44") (pintype "bidirectional"))
    )
    (net (code "5") (name "/C1") (class "Default")
      (node (ref "D27") (pin "2") (pinfunction "A_2") (pintype "passive"))
      (node (ref "J5") (pin "15") (pinfunction "15_15") (pintype "passive"))
      (node (ref "Q24") (pin "2") (pinfunction "S_2") (pintype "passive"))
      (node (ref "R76") (pin "1") (pinfunction "1_1") (pintype "passive"))
      (node (ref "R77") (pin "2") (pinfunction "2_2") (pintype "passive"))
    )
    (net (code "6") (name "/C2") (class "Default")
      (node (ref "D26") (pin "2") (pinfunction "A_2") (pintype "passive"))
      (node (ref "J5") (pin "14") (pinfunction "14_14") (pintype "passive"))
      (node (ref "Q23") (pin "2") (pinfunction "S_2") (pintype "passive"))
      (node (ref "R73") (pin "1") (pinfunction "1_1") (pintype "passive"))
      (node (ref "R74") (pin "2") (pinfunction "2_2") (pintype "passive"))
    )
    (net (code "7") (name "/C3") (class "Default")
      (node (ref "D25") (pin "2") (pinfunction "A_2") (pintype "passive"))
      (node (ref "J5") (pin "13") (pinfunction "13_13") (pintype "passive"))
      (node (ref "Q22") (pin "2") (pinfunction "S_2") (pintype "passive"))
      (node (ref "R70") (pin "1") (pinfunction "1_1") (pintype "passive"))
      (node (ref "R71") (pin "2") (pinfunction "2_2") (pintype "passive"))
    )
    (net (code "8") (name "/C4") (class "Default")
      (node (ref "D24") (pin "2") (pinfunction "A_2") (pintype "passive"))
      (node (ref "J5") (pin "12") (pinfunction "12_12") (pintype "passive"))
      (node (ref "Q21") (pin "2") (pinfunction "S_2") (pintype "passive"))
      (node (ref "R67") (pin "1") (pinfunction "1_1") (pintype "passive"))
      (node (ref "R68") (pin "2") (pinfunction "2_2") (pintype "passive"))
    )
    (net (code "9") (name "/C6") (class "Default")
      (node (ref "D21") (pin "2") (pinfunction "A_2") (pintype "passive"))
      (node (ref "J5") (pin "10") (pinfunction "10_10") (pintype "passive"))
      (node (ref "Q19") (pin "2") (pinfunction "S_2") (pintype "passive"))
      (node (ref "R59") (pin "1") (pinfunction "1_1") (pintype "passive"))
      (node (ref "R60") (pin "2") (pinfunction "2_2") (pintype "passive"))
    )
    (net (code "10") (name "/C7") (class "Default")
      (node (ref "D20") (pin "2") (pinfunction "A_2") (pintype "passive"))
      (node (ref "J5") (pin "9") (pinfunction "9_9") (pintype "passive"))
      (node (ref "Q17") (pin "2") (pinfunction "S_2") (pintype "passive"))
      (node (ref "R55") (pin "1") (pinfunction "1_1") (pintype "passive"))
      (node (ref "R56") (pin "2") (pinfunction "2_2") (pintype "passive"))
    )
    (net (code "11") (name "/C8") (class "Default")
      (node (ref "D19") (pin "2") (pinfunction "A_2") (pintype "passive"))
      (node (ref "J5") (pin "8") (pinfunction "8_8") (pintype "passive"))
      (node (ref "Q16") (pin "2") (pinfunction "S_2") (pintype "passive"))
      (node (ref "R52") (pin "1") (pinfunction "1_1") (pintype "passive"))
      (node (ref "R53") (pin "2") (pinfunction "2_2") (pintype "passive"))
    )
    (net (code "12") (name "/C9") (class "Default")
      (node (ref "D18") (pin "2") (pinfunction "A_2") (pintype "passive"))
      (node (ref "J5") (pin "7") (pinfunction "7_7") (pintype "passive"))
      (node (ref "Q15") (pin "2") (pinfunction "S_2") (pintype "passive"))
      (node (ref "R49") (pin "1") (pinfunction "1_1") (pintype "passive"))
      (node (ref "R50") (pin "2") (pinfunction "2_2") (pintype "passive"))
    )
    (net (code "13") (name "/C11") (class "Default")
      (node (ref "D14") (pin "2") (pinfunction "A_2") (pintype "passive"))
      (node (ref "J5") (pin "5") (pinfunction "5_5") (pintype "passive"))
      (node (ref "Q12") (pin "2") (pinfunction "S_2") (pintype "passive"))
      (node (ref "R37") (pin "1") (pinfunction "1_1") (pintype "passive"))
      (node (ref "R38") (pin "2") (pinfunction "2_2") (pintype "passive"))
    )
    (net (code "14") (name "/C12") (class "Default")
      (node (ref "D13") (pin "2") (pinfunction "A_2") (pintype "passive"))
      (node (ref "J5") (pin "4") (pinfunction "4_4") (pintype "passive"))
      (node (ref "Q10") (pin "2") (pinfunction "S_2") (pintype "passive"))
      (node (ref "R33") (pin "1") (pinfunction "1_1") (pintype "passive"))
      (node (ref "R35") (pin "2") (pinfunction "2_2") (pintype "passive"))
    )
    (net (code "15") (name "/C13") (class "Default")
      (node (ref "D11") (pin "2") (pinfunction "A_2") (pintype "passive"))
      (node (ref "J5") (pin "3") (pinfunction "3_3") (pintype "passive"))
      (node (ref "Q9") (pin "2") (pinfunction "S_2") (pintype "passive"))
      (node (ref "R30") (pin "1") (pinfunction "1_1") (pintype "passive"))
      (node (ref "R31") (pin "2") (pinfunction "2_2") (pintype "passive"))
    )
    (net (code "16") (name "/C14") (class "Default")
      (node (ref "D9") (pin "2") (pinfunction "A_2") (pintype "passive"))
      (node (ref "J5") (pin "2") (pinfunction "2_2") (pintype "passive"))
      (node (ref "Q8") (pin "2") (pinfunction "S_2") (pintype "passive"))
      (node (ref "R25") (pin "1") (pinfunction "1_1") (pintype "passive"))
      (node (ref "R28") (pin "2") (pinfunction "2_2") (pintype "passive"))
    )
    (net (code "17") (name "/CAP1") (class "Default")
      (node (ref "C28") (pin "2") (pinfunction "2_2") (pintype "passive"))
      (node (ref "Q18") (pin "1") (pinfunction "B_1") (pintype "passive"))
      (node (ref "U2") (pin "7") (pinfunction "CAP1_7") (pintype "passive"))
    )
    (net (code "18") (name "/CAP2") (class "Default")
      (node (ref "C25") (pin "2") (pinfunction "2_2") (pintype "passive"))
      (node (ref "U2") (pin "11") (pinfunction "NC_11") (pintype "passive"))
      (node (ref "U2") (pin "12") (pinfunction "NC_12") (pintype "passive"))
      (node (ref "U2") (pin "14") (pinfunction "CAP2_14") (pintype "passive"))
    )
    (net (code "19") (name "/CAP3") (class "Default")
      (node (ref "C23") (pin "2") (pinfunction "2_2") (pintype "passive"))
      (node (ref "U2") (pin "16") (pinfunction "NC_16") (pintype "passive"))
      (node (ref "U2") (pin "17") (pinfunction "NC_17") (pintype "passive"))
      (node (ref "U2") (pin "19") (pinfunction "CAP3_19") (pintype "passive"))
    )
    (net (code "20") (name "/CHG_EN") (class "Default")
      (node (ref "U2") (pin "2") (pinfunction "CHG_2") (pintype "power_in+no_connect"))
    )
    (net (code "21") (name "/DSG_EN") (class "Default")
      (node (ref "U2") (pin "1") (pinfunction "DSG_1") (pintype "power_in+no_connect"))
    )
    (net (code "22") (name "/RSN") (class "Default")
      (node (ref "R80") (pin "1") (pinfunction "1_1") (pintype "passive"))
    )
    (net (code "23") (name "/RSP") (class "Default")
      (node (ref "R81") (pin "1") (pinfunction "1_1") (pintype "passive"))
    )
    (net (code "24") (name "/SCL") (class "Default")
      (node (ref "U2") (pin "5") (pinfunction "SCL_5") (pintype "bidirectional"))
    )
    (net (code "25") (name "/SDA") (class "Default")
      (node (ref "U2") (pin "4") (pinfunction "SDA_4") (pintype "bidirectional"))
    )
    (net (code "26") (name "/SRN") (class "Default")
      (node (ref "C41") (pin "1") (pinfunction "1_1") (pintype "passive"))
      (node (ref "C42") (pin "2") (pinfunction "2_2") (pintype "passive"))
      (node (ref "R80") (pin "2") (pinfunction "2_2") (pintype "passive"))
      (node (ref "U2") (pin "43") (pinfunction "SRN_43") (pintype "input"))
    )
    (net (code "27") (name "/SRP") (class "Default")
      (node (ref "C42") (pin "1") (pinfunction "1_1") (pintype "passive"))
      (node (ref "C43") (pin "2") (pinfunction "2_2") (pintype "passive"))
      (node (ref "R81") (pin "2") (pinfunction "2_2") (pintype "passive"))
      (node (ref "U2") (pin "42") (pinfunction "SRP_42") (pintype "input"))
    )
    (net (code "28") (name "/TS1") (class "Default")
      (node (ref "C27") (pin "2") (pinfunction "2_2") (pintype "passive"))
      (node (ref "D10") (pin "1") (pinfunction "K_1") (pintype "passive"))
      (node (ref "RT3") (pin "2") (pinfunction "2_2") (pintype "passive"))
      (node (ref "U2") (pin "6") (pinfunction "TS1_6") (pintype "input"))
    )
    (net (code "29") (name "/TS2") (class "Default")
      (node (ref "C24") (pin "2") (pinfunction "2_2") (pintype "passive"))
      (node (ref "RT2") (pin "2") (pinfunction "2_2") (pintype "passive"))
      (node (ref "U2") (pin "13") (pinfunction "TS2_13") (pintype "input"))
    )
    (net (code "30") (name "/TS3") (class "Default")
      (node (ref "C22") (pin "2") (pinfunction "2_2") (pintype "passive"))
      (node (ref "RT1") (pin "2") (pinfunction "2_2") (pintype "passive"))
      (node (ref "U2") (pin "18") (pinfunction "TS3_18") (pintype "input"))
    )
    (net (code "31") (name "/VC5X") (class "Default")
      (node (ref "C17") (pin "1") (pinfunction "1_1") (pintype "passive"))
      (node (ref "C19") (pin "2") (pinfunction "2_2") (pintype "passive"))
      (node (ref "C24") (pin "1") (pinfunction "1_1") (pintype "passive"))
      (node (ref "C25") (pin "1") (pinfunction "1_1") (pintype "passive"))
      (node (ref "C33") (pin "1") (pinfunction "1_1") (pintype "passive"))
      (node (ref "C34") (pin "1") (pinfunction "1_1") (pintype "passive"))
      (node (ref "D23") (pin "1") (pinfunction "K_1") (pintype "passive"))
      (node (ref "R47") (pin "1") (pinfunction "1_1") (pintype "passive"))
      (node (ref "R63") (pin "2") (pinfunction "2_2") (pintype "passive"))
      (node (ref "RT2") (pin "1") (pinfunction "1_1") (pintype "passive"))
      (node (ref "TP11") (pin "1") (pinfunction "1_1") (pintype "passive"))
      (node (ref "U2") (pin "10") (pinfunction "VC5X_10") (pintype "input"))
    )
    (net (code "32") (name "/VC10X") (class "Default")
      (node (ref "C13") (pin "1") (pinfunction "1_1") (pintype "passive"))
      (node (ref "C14") (pin "1") (pinfunction "1_1") (pintype "passive"))
      (node (ref "C15") (pin "1") (pinfunction "1_1") (pintype "passive"))
      (node (ref "C17") (pin "2") (pinfunction "2_2") (pintype "passive"))
      (node (ref "C22") (pin "1") (pinfunction "1_1") (pintype "passive"))
      (node (ref "C23") (pin "1") (pinfunction "1_1") (pintype "passive"))
      (node (ref "D17") (pin "1") (pinfunction "K_1") (pintype "passive"))
      (node (ref "R43") (pin "2") (pinfunction "2_2") (pintype "passive"))
      (node (ref "RT1") (pin "1") (pinfunction "1_1") (pintype "passive"))
      (node (ref "TP10") (pin "1") (pinfunction "1_1") (pintype "passive"))
      (node (ref "U2") (pin "15") (pinfunction "VC10X_15") (pintype "input"))
    )
    (net (code "33") (name "/VC15X") (class "Default")
      (node (ref "C15") (pin "2") (pinfunction "2_2") (pintype "passive"))
      (node (ref "D8") (pin "1") (pinfunction "K_1") (pintype "passive"))
      (node (ref "R20") (pin "2") (pinfunction "2_2") (pintype "passive"))
      (node (ref "TP9") (pin "1") (pinfunction "1_1") (pintype "passive"))
      (node (ref "U2") (pin "20") (pinfunction "BAT_20") (pintype "power_in"))
    )
    (net (code "34") (name "/WAKE") (class "Default")
      (node (ref "RDNP6") (pin "1") (pinfunction "1_1") (pintype "passive"))
    )
    (net (code "37") (name "B0") (class "Default")
      (node (ref "D28") (pin "2") (pinfunction "A_2") (pintype "passive"))
      (node (ref "J5") (pin "16") (pinfunction "16_16") (pintype "passive"))
      (node (ref "Q25") (pin "2") (pinfunction "S_2") (pintype "passive"))
      (node (ref "R79") (pin "1") (pinfunction "1_1") (pintype "passive"))
    )
    (net (code "38") (name "B15") (class "Default")
      (node (ref "C8") (pin "2") (pinfunction "2_2") (pintype "passive"))
      (node (ref "D16") (pin "2") (pinfunction "A_2") (pintype "passive"))
      (node (ref "J5") (pin "1") (pinfunction "1_1") (pintype "passive"))
      (node (ref "R20") (pin "1") (pinfunction "1_1") (pintype "passive"))
      (node (ref "R22") (pin "1") (pinfunction "1_1") (pintype "passive"))
      (node (ref "R23") (pin "2") (pinfunction "2_2") (pintype "passive"))
      (node (ref "R41") (pin "2") (pinfunction "2_2") (pintype "passive"))
      (node (ref "R42") (pin "2") (pinfunction "2_2") (pintype "passive"))
    )
    (net (code "39") (name "C5") (class "Default")
      (node (ref "D22") (pin "2") (pinfunction "A_2") (pintype "passive"))
      (node (ref "J5") (pin "11") (pinfunction "11_11") (pintype "passive"))
      (node (ref "Q20") (pin "2") (pinfunction "S_2") (pintype "passive"))
      (node (ref "R62") (pin "1") (pinfunction "1_1") (pintype "passive"))
      (node (ref "R63") (pin "1") (pinfunction "1_1") (pintype "passive"))
      (node (ref "R64") (pin "1") (pinfunction "1_1") (pintype "passive"))
      (node (ref "R65") (pin "2") (pinfunction "2_2") (pintype "passive"))
    )
    (net (code "40") (name "C10") (class "Default")
      (node (ref "D15") (pin "2") (pinfunction "A_2") (pintype "passive"))
      (node (ref "J5") (pin "6") (pinfunction "6_6") (pintype "passive"))
      (node (ref "Q13") (pin "2") (pinfunction "S_2") (pintype "passive"))
      (node (ref "R40") (pin "1") (pinfunction "1_1") (pintype "passive"))
      (node (ref "R43") (pin "1") (pinfunction "1_1") (pintype "passive"))
      (node (ref "R45") (pin "1") (pinfunction "1_1") (pintype "passive"))
      (node (ref "R46") (pin "2") (pinfunction "2_2") (pintype "passive"))
    )
    (net (code "41") (name "GND") (class "Default")
      (node (ref "C18") (pin "1") (pinfunction "1_1") (pintype "passive"))
      (node (ref "C19") (pin "1") (pinfunction "1_1") (pintype "passive"))
      (node (ref "C21") (pin "1") (pinfunction "1_1") (pintype "passive"))
      (node (ref "C27") (pin "1") (pinfunction "1_1") (pintype "passive"))
      (node (ref "C28") (pin "1") (pinfunction "1_1") (pintype "passive"))
      (node (ref "C29") (pin "1") (pinfunction "1_1") (pintype "passive"))
      (node (ref "C31") (pin "1") (pinfunction "1_1") (pintype "passive"))
      (node (ref "C32") (pin "1") (pinfunction "1_1") (pintype "passive"))
      (node (ref "C40") (pin "1") (pinfunction "1_1") (pintype "passive"))
      (node (ref "C41") (pin "2") (pinfunction "2_2") (pintype "passive"))
      (node (ref "C43") (pin "1") (pinfunction "1_1") (pintype "passive"))
      (node (ref "D12") (pin "2") (pinfunction "A_2") (pintype "passive"))
      (node (ref "DDNP1") (pin "2") (pinfunction "A_2") (pintype "passive"))
      (node (ref "Q11") (pin "2") (pinfunction "S_2") (pintype "passive"))
      (node (ref "R27") (pin "1") (pinfunction "1_1") (pintype "passive"))
      (node (ref "R58") (pin "1") (pinfunction "1_1") (pintype "passive"))
      (node (ref "RT3") (pin "1") (pinfunction "1_1") (pintype "passive"))
      (node (ref "U2") (pin "3") (pinfunction "VSS_3") (pintype "power_in"))
    )
    (net (code "42") (name "LEDP") (class "Default")
      (node (ref "C32") (pin "2") (pinfunction "2_2") (pintype "passive"))
      (node (ref "Q18") (pin "3") (pinfunction "E_3") (pintype "passive"))
    )
    (net (code "43") (name "Net-(D7-A)") (class "Default")
      (node (ref "C8") (pin "1") (pinfunction "1_1") (pintype "passive"))
      (node (ref "D7") (pin "2") (pinfunction "A_2") (pintype "passive"))
      (node (ref "Q6") (pin "1") (pinfunction "G_1") (pintype "passive"))
      (node (ref "R19") (pin "1") (pinfunction "1_1") (pintype "passive"))
    )
    (net (code "44") (name "Net-(D8-A)") (class "Default")
      (node (ref "C9") (pin "2") (pinfunction "2_2") (pintype "passive"))
      (node (ref "D8") (pin "2") (pinfunction "A_2") (pintype "passive"))
      (node (ref "R22") (pin "2") (pinfunction "2_2") (pintype "passive"))
      (node (ref "U2") (pin "24") (pinfunction "VC15_24") (pintype "input"))
    )
    (net (code "45") (name "Net-(D9-K)") (class "Default")
      (node (ref "D9") (pin "1") (pinfunction "K_1") (pintype "passive"))
      (node (ref "Q8") (pin "1") (pinfunction "G_1") (pintype "passive"))
      (node (ref "R24") (pin "1") (pinfunction "1_1") (pintype "passive"))
    )
    (net (code "46") (name "Net-(D10-A)") (class "Default")
      (node (ref "D10") (pin "2") (pinfunction "A_2") (pintype "passive"))
      (node (ref "D12") (pin "1") (pinfunction "K_1") (pintype "passive"))
      (node (ref "R26") (pin "1") (pinfunction "1_1") (pintype "passive"))
      (node (ref "RDNP5") (pin "2") (pinfunction "2_2") (pintype "passive"))
    )
    (net (code "47") (name "Net-(D11-K)") (class "Default")
      (node (ref "D11") (pin "1") (pinfunction "K_1") (pintype "passive"))
      (node (ref "Q9") (pin "1") (pinfunction "G_1") (pintype "passive"))
      (node (ref "R29") (pin "1") (pinfunction "1_1") (pintype "passive"))
    )
    (net (code "48") (name "Net-(D13-K)") (class "Default")
      (node (ref "D13") (pin "1") (pinfunction "K_1") (pintype "passive"))
      (node (ref "Q10") (pin "1") (pinfunction "G_1") (pintype "passive"))
      (node (ref "R32") (pin "1") (pinfunction "1_1") (pintype "passive"))
    )
    (net (code "49") (name "Net-(D14-K)") (class "Default")
      (node (ref "D14") (pin "1") (pinfunction "K_1") (pintype "passive"))
      (node (ref "Q12") (pin "1") (pinfunction "G_1") (pintype "passive"))
      (node (ref "R36") (pin "1") (pinfunction "1_1") (pintype "passive"))
    )
    (net (code "50") (name "Net-(D15-K)") (class "Default")
      (node (ref "D15") (pin "1") (pinfunction "K_1") (pintype "passive"))
      (node (ref "Q13") (pin "1") (pinfunction "G_1") (pintype "passive"))
      (node (ref "R39") (pin "1") (pinfunction "1_1") (pintype "passive"))
    )
    (net (code "51") (name "Net-(D16-K)") (class "Default")
      (node (ref "D16") (pin "1") (pinfunction "K_1") (pintype "passive"))
      (node (ref "R41") (pin "1") (pinfunction "1_1") (pintype "passive"))
      (node (ref "R44") (pin "2") (pinfunction "2_2") (pintype "passive"))
    )
    (net (code "52") (name "Net-(D17-A)") (class "Default")
      (node (ref "C16") (pin "2") (pinfunction "2_2") (pintype "passive"))
      (node (ref "D17") (pin "2") (pinfunction "A_2") (pintype "passive"))
      (node (ref "R45") (pin "2") (pinfunction "2_2") (pintype "passive"))
      (node (ref "U2") (pin "30") (pinfunction "VC10_30") (pintype "input"))
    )
    (net (code "53") (name "Net-(D18-K)") (class "Default")
      (node (ref "D18") (pin "1") (pinfunction "K_1") (pintype "passive"))
      (node (ref "Q15") (pin "1") (pinfunction "G_1") (pintype "passive"))
      (node (ref "R48") (pin "1") (pinfunction "1_1") (pintype "passive"))
    )
    (net (code "54") (name "Net-(D19-K)") (class "Default")
      (node (ref "D19") (pin "1") (pinfunction "K_1") (pintype "passive"))
      (node (ref "Q16") (pin "1") (pinfunction "G_1") (pintype "passive"))
      (node (ref "R51") (pin "1") (pinfunction "1_1") (pintype "passive"))
    )
    (net (code "55") (name "Net-(D20-K)") (class "Default")
      (node (ref "D20") (pin "1") (pinfunction "K_1") (pintype "passive"))
      (node (ref "Q17") (pin "1") (pinfunction "G_1") (pintype "passive"))
      (node (ref "R54") (pin "1") (pinfunction "1_1") (pintype "passive"))
    )
    (net (code "56") (name "Net-(D21-K)") (class "Default")
      (node (ref "D21") (pin "1") (pinfunction "K_1") (pintype "passive"))
      (node (ref "Q19") (pin "1") (pinfunction "G_1") (pintype "passive"))
      (node (ref "R57") (pin "1") (pinfunction "1_1") (pintype "passive"))
    )
    (net (code "57") (name "Net-(D22-K)") (class "Default")
      (node (ref "D22") (pin "1") (pinfunction "K_1") (pintype "passive"))
      (node (ref "Q20") (pin "1") (pinfunction "G_1") (pintype "passive"))
      (node (ref "R61") (pin "1") (pinfunction "1_1") (pintype "passive"))
    )
    (net (code "58") (name "Net-(D23-A)") (class "Default")
      (node (ref "C35") (pin "2") (pinfunction "2_2") (pintype "passive"))
      (node (ref "D23") (pin "2") (pinfunction "A_2") (pintype "passive"))
      (node (ref "R64") (pin "2") (pinfunction "2_2") (pintype "passive"))
      (node (ref "U2") (pin "36") (pinfunction "VC5_36") (pintype "input"))
    )
    (net (code "59") (name "Net-(D24-K)") (class "Default")
      (node (ref "D24") (pin "1") (pinfunction "K_1") (pintype "passive"))
      (node (ref "Q21") (pin "1") (pinfunction "G_1") (pintype "passive"))
      (node (ref "R66") (pin "1") (pinfunction "1_1") (pintype "passive"))
    )
    (net (code "60") (name "Net-(D25-K)") (class "Default")
      (node (ref "D25") (pin "1") (pinfunction "K_1") (pintype "passive"))
      (node (ref "Q22") (pin "1") (pinfunction "G_1") (pintype "passive"))
      (node (ref "R69") (pin "1") (pinfunction "1_1") (pintype "passive"))
    )
    (net (code "61") (name "Net-(D26-K)") (class "Default")
      (node (ref "D26") (pin "1") (pinfunction "K_1") (pintype "passive"))
      (node (ref "Q23") (pin "1") (pinfunction "G_1") (pintype "passive"))
      (node (ref "R72") (pin "1") (pinfunction "1_1") (pintype "passive"))
    )
    (net (code "62") (name "Net-(D27-K)") (class "Default")
      (node (ref "D27") (pin "1") (pinfunction "K_1") (pintype "passive"))
      (node (ref "Q24") (pin "1") (pinfunction "G_1") (pintype "passive"))
      (node (ref "R75") (pin "1") (pinfunction "1_1") (pintype "passive"))
    )
    (net (code "63") (name "Net-(D28-K)") (class "Default")
      (node (ref "D28") (pin "1") (pinfunction "K_1") (pintype "passive"))
      (node (ref "Q25") (pin "1") (pinfunction "G_1") (pintype "passive"))
      (node (ref "R78") (pin "1") (pinfunction "1_1") (pintype "passive"))
    )
    (net (code "64") (name "Net-(DDNP1-K)") (class "Default")
      (node (ref "DDNP1") (pin "1") (pinfunction "K_1") (pintype "passive"))
      (node (ref "RDNP5") (pin "1") (pinfunction "1_1") (pintype "passive"))
      (node (ref "RDNP6") (pin "2") (pinfunction "2_2") (pintype "passive"))
    )
    (net (code "65") (name "Net-(Q6-D)") (class "Default")
      (node (ref "Q6") (pin "3") (pinfunction "D_3") (pintype "passive"))
      (node (ref "Q7") (pin "3") (pinfunction "D_3") (pintype "passive"))
      (node (ref "R21") (pin "2") (pinfunction "2_2") (pintype "passive"))
    )
    (net (code "66") (name "Net-(Q7-S)") (class "Default")
      (node (ref "Q7") (pin "2") (pinfunction "S_2") (pintype "passive"))
      (node (ref "R26") (pin "2") (pinfunction "2_2") (pintype "passive"))
    )
    (net (code "67") (name "Net-(Q8-D)") (class "Default")
      (node (ref "Q8") (pin "3") (pinfunction "D_3") (pintype "passive"))
      (node (ref "R23") (pin "1") (pinfunction "1_1") (pintype "passive"))
    )
    (net (code "68") (name "Net-(Q9-D)") (class "Default")
      (node (ref "Q9") (pin "3") (pinfunction "D_3") (pintype "passive"))
      (node (ref "R28") (pin "1") (pinfunction "1_1") (pintype "passive"))
    )
    (net (code "69") (name "Net-(Q10-D)") (class "Default")
      (node (ref "Q10") (pin "3") (pinfunction "D_3") (pintype "passive"))
      (node (ref "R31") (pin "1") (pinfunction "1_1") (pintype "passive"))
    )
    (net (code "70") (name "Net-(Q11-D)") (class "Default")
      (node (ref "Q11") (pin "3") (pinfunction "D_3") (pintype "passive"))
      (node (ref "Q7") (pin "1") (pinfunction "G_1") (pintype "passive"))
      (node (ref "R21") (pin "1") (pinfunction "1_1") (pintype "passive"))
      (node (ref "R27") (pin "2") (pinfunction "2_2") (pintype "passive"))
    )
    (net (code "71") (name "Net-(Q11-G)") (class "Default")
      (node (ref "Q11") (pin "1") (pinfunction "G_1") (pintype "passive"))
      (node (ref "R34") (pin "1") (pinfunction "1_1") (pintype "passive"))
    )
    (net (code "72") (name "Net-(Q12-D)") (class "Default")
      (node (ref "Q12") (pin "3") (pinfunction "D_3") (pintype "passive"))
      (node (ref "R35") (pin "1") (pinfunction "1_1") (pintype "passive"))
    )
    (net (code "73") (name "Net-(Q13-D)") (class "Default")
      (node (ref "Q13") (pin "3") (pinfunction "D_3") (pintype "passive"))
      (node (ref "R38") (pin "1") (pinfunction "1_1") (pintype "passive"))
    )
    (net (code "74") (name "Net-(Q14-D)") (class "Default")
      (node (ref "C18") (pin "2") (pinfunction "2_2") (pintype "passive"))
      (node (ref "Q14") (pin "3") (pinfunction "D_3") (pintype "passive"))
      (node (ref "R44") (pin "1") (pinfunction "1_1") (pintype "passive"))
    )
    (net (code "75") (name "Net-(Q14-G)") (class "Default")
      (node (ref "Q14") (pin "1") (pinfunction "G_1") (pintype "passive"))
      (node (ref "R47") (pin "2") (pinfunction "2_2") (pintype "passive"))
    )
    (net (code "76") (name "Net-(Q15-D)") (class "Default")
      (node (ref "Q15") (pin "3") (pinfunction "D_3") (pintype "passive"))
      (node (ref "R46") (pin "1") (pinfunction "1_1") (pintype "passive"))
    )
    (net (code "77") (name "Net-(Q16-D)") (class "Default")
      (node (ref "Q16") (pin "3") (pinfunction "D_3") (pintype "passive"))
      (node (ref "R50") (pin "1") (pinfunction "1_1") (pintype "passive"))
    )
    (net (code "78") (name "Net-(Q17-D)") (class "Default")
      (node (ref "Q17") (pin "3") (pinfunction "D_3") (pintype "passive"))
      (node (ref "R53") (pin "1") (pinfunction "1_1") (pintype "passive"))
    )
    (net (code "79") (name "Net-(Q18-C-Pad2)") (class "Default")
      (node (ref "Q18") (pin "2") (pinfunction "C_2") (pintype "passive"))
      (node (ref "Q18") (pin "4") (pinfunction "C_4") (pintype "passive"))
      (node (ref "R42") (pin "1") (pinfunction "1_1") (pintype "passive"))
    )
    (net (code "80") (name "Net-(Q19-D)") (class "Default")
      (node (ref "Q19") (pin "3") (pinfunction "D_3") (pintype "passive"))
      (node (ref "R56") (pin "1") (pinfunction "1_1") (pintype "passive"))
    )
    (net (code "81") (name "Net-(Q20-D)") (class "Default")
      (node (ref "Q20") (pin "3") (pinfunction "D_3") (pintype "passive"))
      (node (ref "R60") (pin "1") (pinfunction "1_1") (pintype "passive"))
    )
    (net (code "82") (name "Net-(Q21-D)") (class "Default")
      (node (ref "Q21") (pin "3") (pinfunction "D_3") (pintype "passive"))
      (node (ref "R65") (pin "1") (pinfunction "1_1") (pintype "passive"))
    )
    (net (code "83") (name "Net-(Q22-D)") (class "Default")
      (node (ref "Q22") (pin "3") (pinfunction "D_3") (pintype "passive"))
      (node (ref "R68") (pin "1") (pinfunction "1_1") (pintype "passive"))
    )
    (net (code "84") (name "Net-(Q23-D)") (class "Default")
      (node (ref "Q23") (pin "3") (pinfunction "D_3") (pintype "passive"))
      (node (ref "R71") (pin "1") (pinfunction "1_1") (pintype "passive"))
    )
    (net (code "85") (name "Net-(Q24-D)") (class "Default")
      (node (ref "Q24") (pin "3") (pinfunction "D_3") (pintype "passive"))
      (node (ref "R74") (pin "1") (pinfunction "1_1") (pintype "passive"))
    )
    (net (code "86") (name "Net-(Q25-D)") (class "Default")
      (node (ref "Q25") (pin "3") (pinfunction "D_3") (pintype "passive"))
      (node (ref "R77") (pin "1") (pinfunction "1_1") (pintype "passive"))
    )
    (net (code "87") (name "Net-(U2-VC0)") (class "Default")
      (node (ref "C39") (pin "1") (pinfunction "1_1") (pintype "passive"))
      (node (ref "C40") (pin "2") (pinfunction "2_2") (pintype "passive"))
      (node (ref "R78") (pin "2") (pinfunction "2_2") (pintype "passive"))
      (node (ref "R79") (pin "2") (pinfunction "2_2") (pintype "passive"))
      (node (ref "U2") (pin "41") (pinfunction "VC0_41") (pintype "input"))
    )
    (net (code "88") (name "Net-(U2-VC1)") (class "Default")
      (node (ref "C38") (pin "1") (pinfunction "1_1") (pintype "passive"))
      (node (ref "C39") (pin "2") (pinfunction "2_2") (pintype "passive"))
      (node (ref "R75") (pin "2") (pinfunction "2_2") (pintype "passive"))
      (node (ref "R76") (pin "2") (pinfunction "2_2") (pintype "passive"))
      (node (ref "U2") (pin "40") (pinfunction "VC1_40") (pintype "input"))
    )
    (net (code "89") (name "Net-(U2-VC2)") (class "Default")
      (node (ref "C37") (pin "1") (pinfunction "1_1") (pintype "passive"))
      (node (ref "C38") (pin "2") (pinfunction "2_2") (pintype "passive"))
      (node (ref "R72") (pin "2") (pinfunction "2_2") (pintype "passive"))
      (node (ref "R73") (pin "2") (pinfunction "2_2") (pintype "passive"))
      (node (ref "U2") (pin "39") (pinfunction "VC2_39") (pintype "input"))
    )
    (net (code "90") (name "Net-(U2-VC3)") (class "Default")
      (node (ref "C36") (pin "1") (pinfunction "1_1") (pintype "passive"))
      (node (ref "C37") (pin "2") (pinfunction "2_2") (pintype "passive"))
      (node (ref "R69") (pin "2") (pinfunction "2_2") (pintype "passive"))
      (node (ref "R70") (pin "2") (pinfunction "2_2") (pintype "passive"))
      (node (ref "RDNP8") (pin "1") (pinfunction "1_1") (pintype "passive"))
      (node (ref "U2") (pin "38") (pinfunction "VC3_38") (pintype "input"))
    )
    (net (code "91") (name "Net-(U2-VC4)") (class "Default")
      (node (ref "C35") (pin "1") (pinfunction "1_1") (pintype "passive"))
      (node (ref "C36") (pin "2") (pinfunction "2_2") (pintype "passive"))
      (node (ref "R66") (pin "2") (pinfunction "2_2") (pintype "passive"))
      (node (ref "R67") (pin "2") (pinfunction "2_2") (pintype "passive"))
      (node (ref "RDNP8") (pin "2") (pinfunction "2_2") (pintype "passive"))
      (node (ref "U2") (pin "37") (pinfunction "VC4_37") (pintype "input"))
    )
    (net (code "92") (name "Net-(U2-VC5B)") (class "Default")
      (node (ref "C34") (pin "2") (pinfunction "2_2") (pintype "passive"))
      (node (ref "R61") (pin "2") (pinfunction "2_2") (pintype "passive"))
      (node (ref "R62") (pin "2") (pinfunction "2_2") (pintype "passive"))
      (node (ref "U2") (pin "35") (pinfunction "VC5B_35") (pintype "input"))
    )
    (net (code "93") (name "Net-(U2-VC6)") (class "Default")
      (node (ref "C30") (pin "1") (pinfunction "1_1") (pintype "passive"))
      (node (ref "C33") (pin "2") (pinfunction "2_2") (pintype "passive"))
      (node (ref "R57") (pin "2") (pinfunction "2_2") (pintype "passive"))
      (node (ref "R59") (pin "2") (pinfunction "2_2") (pintype "passive"))
      (node (ref "U2") (pin "34") (pinfunction "VC6_34") (pintype "input"))
    )
    (net (code "94") (name "Net-(U2-VC7)") (class "Default")
      (node (ref "C26") (pin "1") (pinfunction "1_1") (pintype "passive"))
      (node (ref "C30") (pin "2") (pinfunction "2_2") (pintype "passive"))
      (node (ref "R54") (pin "2") (pinfunction "2_2") (pintype "passive"))
      (node (ref "R55") (pin "2") (pinfunction "2_2") (pintype "passive"))
      (node (ref "U2") (pin "33") (pinfunction "VC7_33") (pintype "input"))
    )
    (net (code "95") (name "Net-(U2-VC8)") (class "Default")
      (node (ref "C20") (pin "1") (pinfunction "1_1") (pintype "passive"))
      (node (ref "C26") (pin "2") (pinfunction "2_2") (pintype "passive"))
      (node (ref "R51") (pin "2") (pinfunction "2_2") (pintype "passive"))
      (node (ref "R52") (pin "2") (pinfunction "2_2") (pintype "passive"))
      (node (ref "RDNP7") (pin "1") (pinfunction "1_1") (pintype "passive"))
      (node (ref "U2") (pin "32") (pinfunction "VC8_32") (pintype "input"))
    )
    (net (code "96") (name "Net-(U2-VC9)") (class "Default")
      (node (ref "C16") (pin "1") (pinfunction "1_1") (pintype "passive"))
      (node (ref "C20") (pin "2") (pinfunction "2_2") (pintype "passive"))
      (node (ref "R48") (pin "2") (pinfunction "2_2") (pintype "passive"))
      (node (ref "R49") (pin "2") (pinfunction "2_2") (pintype "passive"))
      (node (ref "RDNP7") (pin "2") (pinfunction "2_2") (pintype "passive"))
      (node (ref "U2") (pin "31") (pinfunction "VC9_31") (pintype "input"))
    )
    (net (code "97") (name "Net-(U2-VC10B)") (class "Default")
      (node (ref "C14") (pin "2") (pinfunction "2_2") (pintype "passive"))
      (node (ref "R39") (pin "2") (pinfunction "2_2") (pintype "passive"))
      (node (ref "R40") (pin "2") (pinfunction "2_2") (pintype "passive"))
      (node (ref "U2") (pin "29") (pinfunction "VC10B_29") (pintype "input"))
    )
    (net (code "98") (name "Net-(U2-VC11)") (class "Default")
      (node (ref "C12") (pin "1") (pinfunction "1_1") (pintype "passive"))
      (node (ref "C13") (pin "2") (pinfunction "2_2") (pintype "passive"))
      (node (ref "R36") (pin "2") (pinfunction "2_2") (pintype "passive"))
      (node (ref "R37") (pin "2") (pinfunction "2_2") (pintype "passive"))
      (node (ref "U2") (pin "28") (pinfunction "VC11_28") (pintype "input"))
    )
    (net (code "99") (name "Net-(U2-VC12)") (class "Default")
      (node (ref "C11") (pin "1") (pinfunction "1_1") (pintype "passive"))
      (node (ref "C12") (pin "2") (pinfunction "2_2") (pintype "passive"))
      (node (ref "R32") (pin "2") (pinfunction "2_2") (pintype "passive"))
      (node (ref "R33") (pin "2") (pinfunction "2_2") (pintype "passive"))
      (node (ref "U2") (pin "27") (pinfunction "VC12_27") (pintype "input"))
    )
    (net (code "100") (name "Net-(U2-VC13)") (class "Default")
      (node (ref "C10") (pin "1") (pinfunction "1_1") (pintype "passive"))
      (node (ref "C11") (pin "2") (pinfunction "2_2") (pintype "passive"))
      (node (ref "R29") (pin "2") (pinfunction "2_2") (pintype "passive"))
      (node (ref "R30") (pin "2") (pinfunction "2_2") (pintype "passive"))
      (node (ref "RDNP4") (pin "1") (pinfunction "1_1") (pintype "passive"))
      (node (ref "U2") (pin "26") (pinfunction "VC13_26") (pintype "input"))
    )
    (net (code "101") (name "Net-(U2-VC14)") (class "Default")
      (node (ref "C10") (pin "2") (pinfunction "2_2") (pintype "passive"))
      (node (ref "C9") (pin "1") (pinfunction "1_1") (pintype "passive"))
      (node (ref "R24") (pin "2") (pinfunction "2_2") (pintype "passive"))
      (node (ref "R25") (pin "2") (pinfunction "2_2") (pintype "passive"))
      (node (ref "RDNP4") (pin "2") (pinfunction "2_2") (pintype "passive"))
      (node (ref "U2") (pin "25") (pinfunction "VC14_25") (pintype "input"))
    )
    (net (code "102") (name "PACK+") (class "Default")
      (node (ref "D7") (pin "1") (pinfunction "K_1") (pintype "passive"))
      (node (ref "Q6") (pin "2") (pinfunction "S_2") (pintype "passive"))
      (node (ref "R19") (pin "2") (pinfunction "2_2") (pintype "passive"))
    )
    (net (code "103") (name "REGOUT") (class "Default")
      (node (ref "C29") (pin "2") (pinfunction "2_2") (pintype "passive"))
      (node (ref "NT2") (pin "1") (pinfunction "1_1") (pintype "passive"))
      (node (ref "R34") (pin "2") (pinfunction "2_2") (pintype "passive"))
      (node (ref "U2") (pin "8") (pinfunction "REGOUT_8") (pintype "power_in"))
    )
    (net (code "104") (name "REGSRC") (class "Default")
      (node (ref "C21") (pin "2") (pinfunction "2_2") (pintype "passive"))
      (node (ref "Q14") (pin "2") (pinfunction "S_2") (pintype "passive"))
      (node (ref "U2") (pin "9") (pinfunction "REGSRC_9") (pintype "power_in"))
    )
    (net (code "105") (name "VCC") (class "Default")
      (node (ref "NT2") (pin "2") (pinfunction "2_2") (pintype "passive"))
    )
    (net (code "106") (name "unconnected-(U2-NC-Pad21)") (class "Default")
      (node (ref "U2") (pin "21") (pinfunction "NC_21") (pintype "passive+no_connect"))
    )
    (net (code "107") (name "unconnected-(U2-NC-Pad22)") (class "Default")
      (node (ref "U2") (pin "22") (pinfunction "NC_22") (pintype "passive+no_connect"))
    )
    (net (code "108") (name "unconnected-(U2-NC-Pad23)") (class "Default")
      (node (ref "U2") (pin "23") (pinfunction "NC_23") (pintype "passive+no_connect"))
    )
  )
)
